# io_board.net
KiCad netlist of a schematic drawn in EAGLE
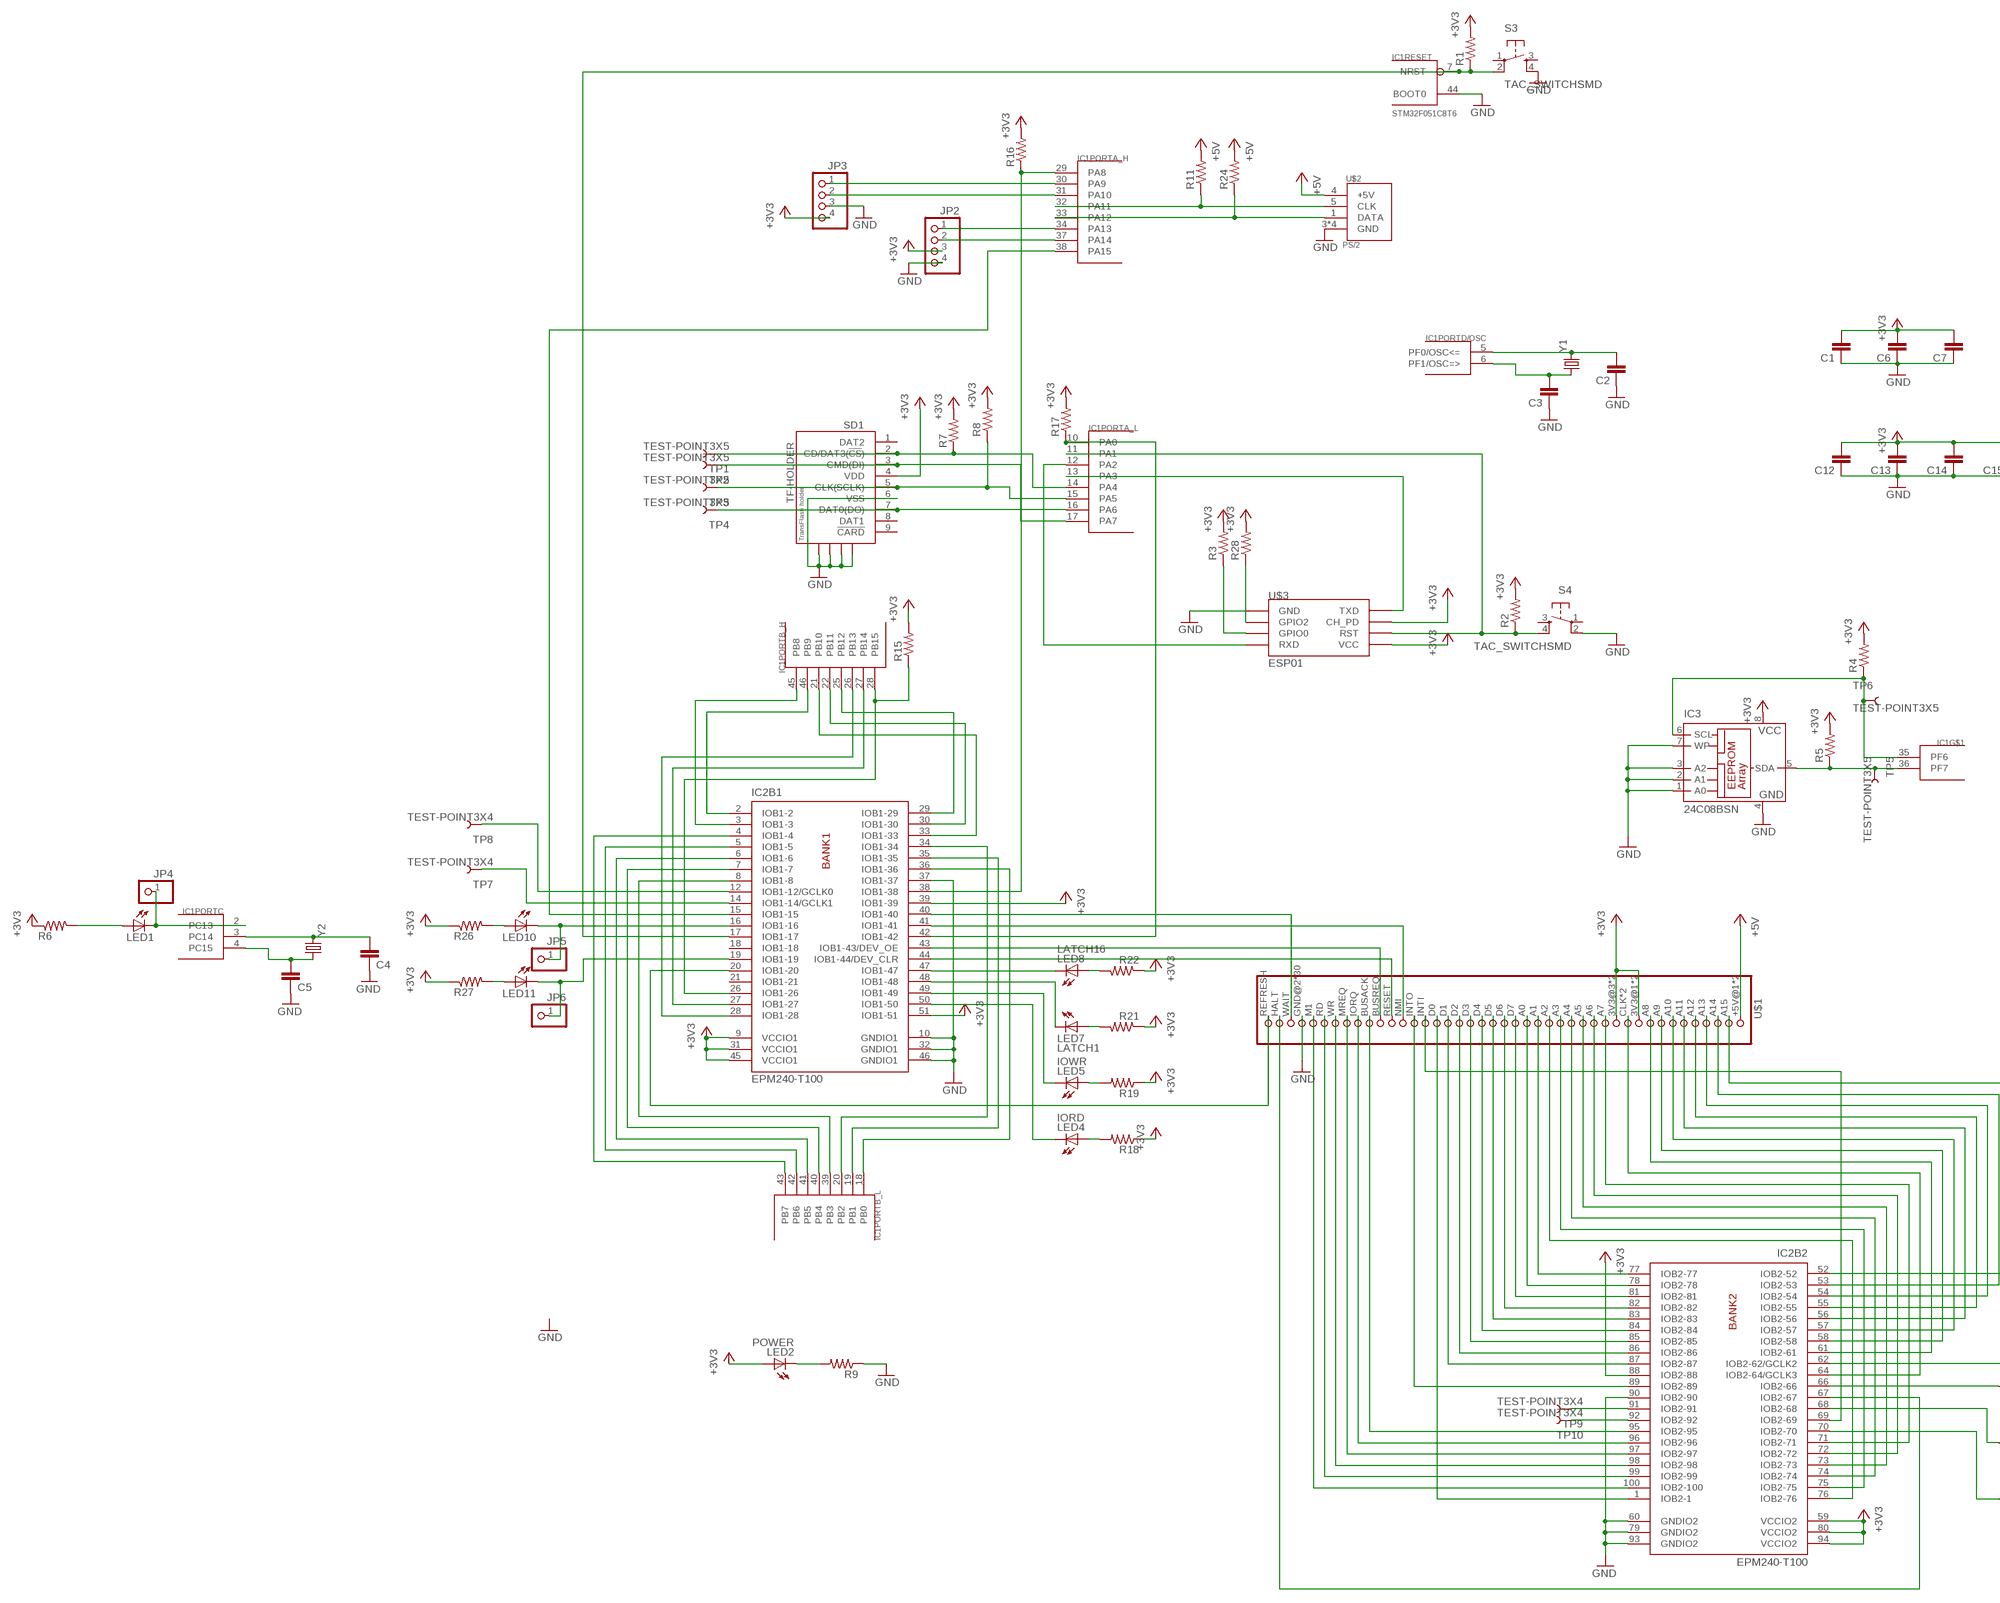
[diagram p0: schematic, sheet 1, part 1 of 2]
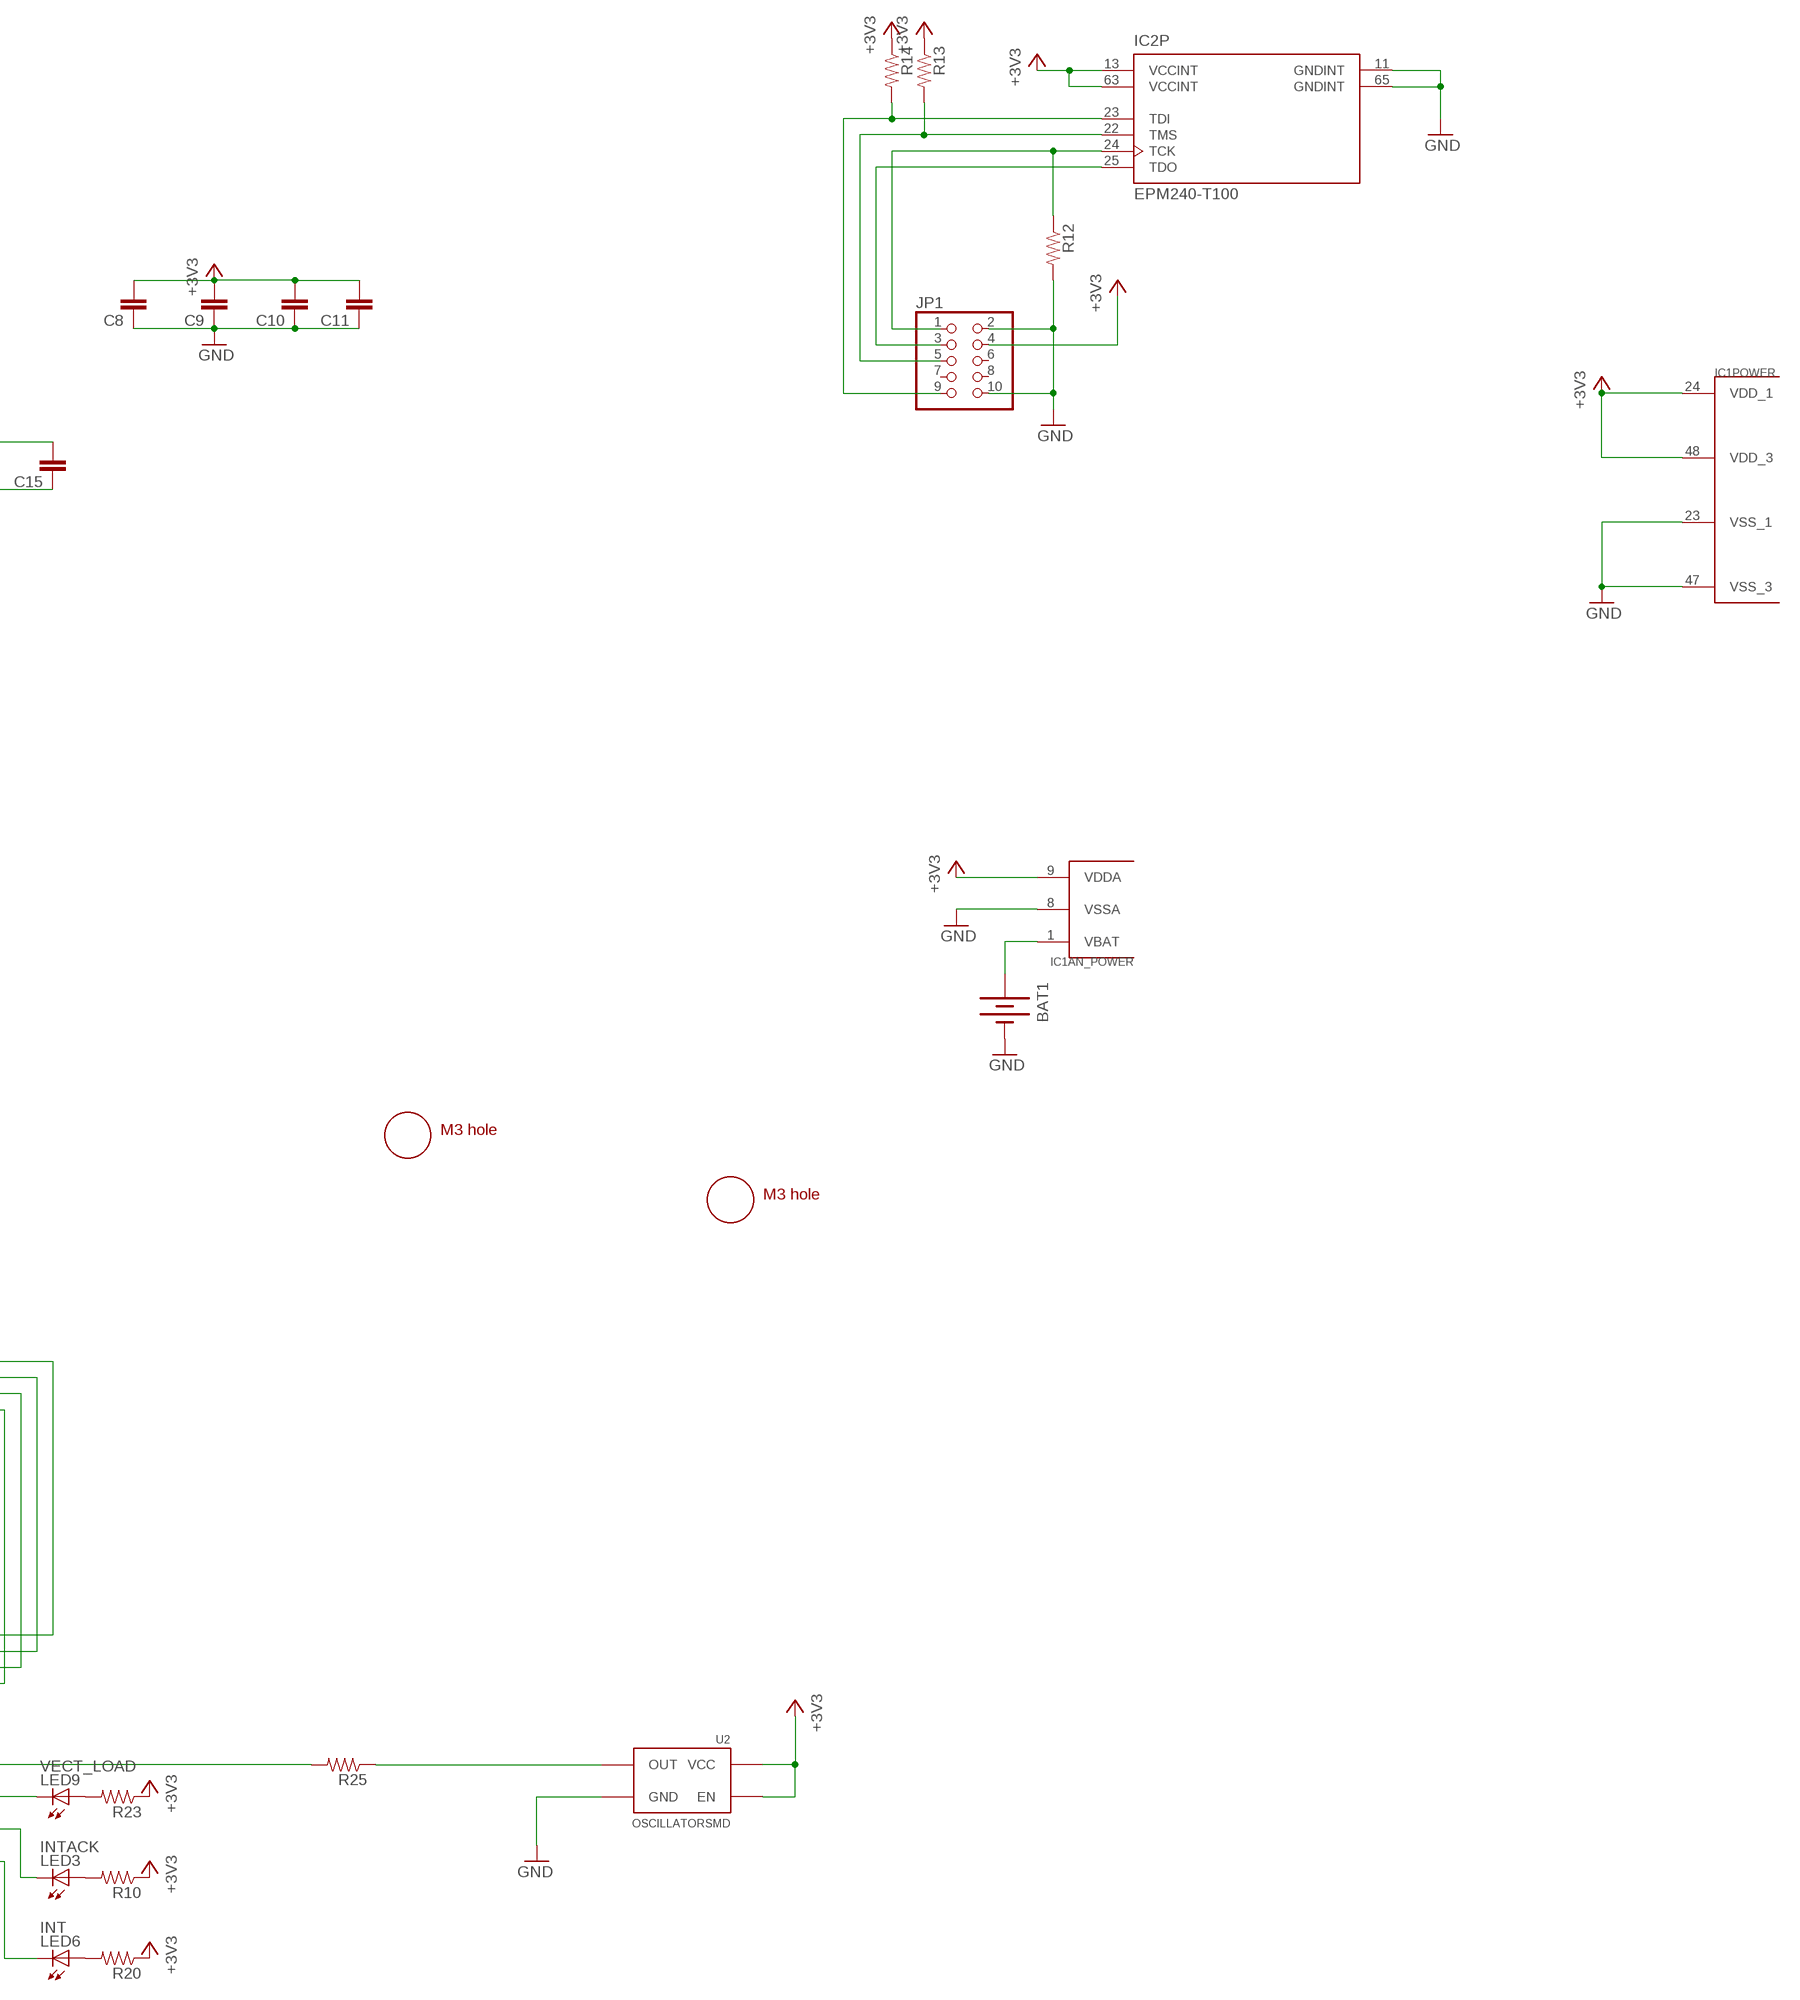
[diagram p1: schematic, sheet 1, part 2 of 2]

(export (version "E")
  (design (tool "Eeschema 10.0.6"))
  (components
    (comp (ref "BAT1")
      (value "BATTERY20PTH")
      (footprint "eagle-import:BATTCOM_20MM_PTH")
      (libsource (lib "eagle-import") (part "BATTERY20PTH"))
    )
    (comp (ref "C1")
      (value "CAP0805")
      (footprint "eagle-import:0805")
      (libsource (lib "eagle-import") (part "CAP0805"))
    )
    (comp (ref "C2")
      (value "CAP0805")
      (footprint "eagle-import:0805")
      (libsource (lib "eagle-import") (part "CAP0805"))
    )
    (comp (ref "C3")
      (value "CAP0805")
      (footprint "eagle-import:0805")
      (libsource (lib "eagle-import") (part "CAP0805"))
    )
    (comp (ref "C4")
      (value "CAP0805")
      (footprint "eagle-import:0805")
      (libsource (lib "eagle-import") (part "CAP0805"))
    )
    (comp (ref "C5")
      (value "CAP0805")
      (footprint "eagle-import:0805")
      (libsource (lib "eagle-import") (part "CAP0805"))
    )
    (comp (ref "C6")
      (value "CAP0805")
      (footprint "eagle-import:0805")
      (libsource (lib "eagle-import") (part "CAP0805"))
    )
    (comp (ref "C7")
      (value "CAP0805")
      (footprint "eagle-import:0805")
      (libsource (lib "eagle-import") (part "CAP0805"))
    )
    (comp (ref "C8")
      (value "CAP0805")
      (footprint "eagle-import:0805")
      (libsource (lib "eagle-import") (part "CAP0805"))
    )
    (comp (ref "C9")
      (value "CAP0805")
      (footprint "eagle-import:0805")
      (libsource (lib "eagle-import") (part "CAP0805"))
    )
    (comp (ref "C10")
      (value "CAP0805")
      (footprint "eagle-import:0805")
      (libsource (lib "eagle-import") (part "CAP0805"))
    )
    (comp (ref "C11")
      (value "CAP0805")
      (footprint "eagle-import:0805")
      (libsource (lib "eagle-import") (part "CAP0805"))
    )
    (comp (ref "C12")
      (value "CAP0805")
      (footprint "eagle-import:0805")
      (libsource (lib "eagle-import") (part "CAP0805"))
    )
    (comp (ref "C13")
      (value "CAP0805")
      (footprint "eagle-import:0805")
      (libsource (lib "eagle-import") (part "CAP0805"))
    )
    (comp (ref "C14")
      (value "CAP0805")
      (footprint "eagle-import:0805")
      (libsource (lib "eagle-import") (part "CAP0805"))
    )
    (comp (ref "C15")
      (value "CAP0805")
      (footprint "eagle-import:0805")
      (libsource (lib "eagle-import") (part "CAP0805"))
    )
    (comp (ref "IC1")
      (value "STM32F051C8T6")
      (footprint "eagle-import:TQFP48")
      (libsource (lib "eagle-import") (part "STM32F051C8T6"))
    )
    (comp (ref "IC2")
      (value "EPM240-T100")
      (footprint "eagle-import:TQFP100")
      (libsource (lib "eagle-import") (part "EPM240-T100"))
    )
    (comp (ref "IC3")
      (value "24C08BSN")
      (footprint "eagle-import:SO-08")
      (fields (field (name "MPN") "AT24C08BN-SH-B"))
      (libsource (lib "eagle-import") (part "24SNC08B"))
    )
    (comp (ref "JP1")
      (value "PINHD-2X5")
      (footprint "eagle-import:2X05")
      (libsource (lib "eagle-import") (part "PINHD-2X5"))
    )
    (comp (ref "JP2")
      (value "PINHD-1X4/90")
      (footprint "eagle-import:1X04_90")
      (libsource (lib "eagle-import") (part "PINHD-1X4/90"))
    )
    (comp (ref "JP3")
      (value "PINHD-1X4/90")
      (footprint "eagle-import:1X04_90")
      (libsource (lib "eagle-import") (part "PINHD-1X4/90"))
    )
    (comp (ref "JP4")
      (value "PINHD-1X1")
      (footprint "eagle-import:1X01")
      (libsource (lib "eagle-import") (part "PINHD-1X1"))
    )
    (comp (ref "JP5")
      (value "PINHD-1X1")
      (footprint "eagle-import:1X01")
      (libsource (lib "eagle-import") (part "PINHD-1X1"))
    )
    (comp (ref "JP6")
      (value "PINHD-1X1")
      (footprint "eagle-import:1X01")
      (libsource (lib "eagle-import") (part "PINHD-1X1"))
    )
    (comp (ref "LED1")
      (value "LEDCHIP-LED0805")
      (footprint "eagle-import:CHIP-LED0805")
      (libsource (lib "eagle-import") (part "LEDCHIP-LED0805"))
    )
    (comp (ref "LED2")
      (value "POWER")
      (footprint "eagle-import:CHIPLED_0805")
      (libsource (lib "eagle-import") (part "LEDCHIPLED_0805"))
    )
    (comp (ref "LED3")
      (value "INTACK")
      (footprint "eagle-import:CHIP-LED0805")
      (libsource (lib "eagle-import") (part "LEDCHIP-LED0805"))
    )
    (comp (ref "LED4")
      (value "IORD")
      (footprint "eagle-import:CHIP-LED0805")
      (libsource (lib "eagle-import") (part "LEDCHIP-LED0805"))
    )
    (comp (ref "LED5")
      (value "IOWR")
      (footprint "eagle-import:CHIP-LED0805")
      (libsource (lib "eagle-import") (part "LEDCHIP-LED0805"))
    )
    (comp (ref "LED6")
      (value "INT")
      (footprint "eagle-import:CHIP-LED0805")
      (libsource (lib "eagle-import") (part "LEDCHIP-LED0805"))
    )
    (comp (ref "LED7")
      (value "LATCH1")
      (footprint "eagle-import:CHIP-LED0805")
      (libsource (lib "eagle-import") (part "LEDCHIP-LED0805"))
    )
    (comp (ref "LED8")
      (value "LATCH16")
      (footprint "eagle-import:CHIP-LED0805")
      (libsource (lib "eagle-import") (part "LEDCHIP-LED0805"))
    )
    (comp (ref "LED9")
      (value "VECT_LOAD")
      (footprint "eagle-import:CHIP-LED0805")
      (libsource (lib "eagle-import") (part "LEDCHIP-LED0805"))
    )
    (comp (ref "LED10")
      (value "LEDCHIP-LED0805")
      (footprint "eagle-import:CHIP-LED0805")
      (libsource (lib "eagle-import") (part "LEDCHIP-LED0805"))
    )
    (comp (ref "LED11")
      (value "LEDCHIP-LED0805")
      (footprint "eagle-import:CHIP-LED0805")
      (libsource (lib "eagle-import") (part "LEDCHIP-LED0805"))
    )
    (comp (ref "R1")
      (value "RESISTOR0805-RES")
      (footprint "eagle-import:0805")
      (libsource (lib "eagle-import") (part "RESISTOR0805-RES"))
    )
    (comp (ref "R2")
      (value "RESISTOR0805-RES")
      (footprint "eagle-import:0805")
      (libsource (lib "eagle-import") (part "RESISTOR0805-RES"))
    )
    (comp (ref "R3")
      (value "RESISTOR0805-RES")
      (footprint "eagle-import:0805")
      (libsource (lib "eagle-import") (part "RESISTOR0805-RES"))
    )
    (comp (ref "R4")
      (value "RESISTOR0805-RES")
      (footprint "eagle-import:0805")
      (libsource (lib "eagle-import") (part "RESISTOR0805-RES"))
    )
    (comp (ref "R5")
      (value "RESISTOR0805-RES")
      (footprint "eagle-import:0805")
      (libsource (lib "eagle-import") (part "RESISTOR0805-RES"))
    )
    (comp (ref "R6")
      (value "RESISTOR0805-RES")
      (footprint "eagle-import:0805")
      (libsource (lib "eagle-import") (part "RESISTOR0805-RES"))
    )
    (comp (ref "R7")
      (value "RESISTOR0805-RES")
      (footprint "eagle-import:0805")
      (libsource (lib "eagle-import") (part "RESISTOR0805-RES"))
    )
    (comp (ref "R8")
      (value "RESISTOR0805-RES")
      (footprint "eagle-import:0805")
      (libsource (lib "eagle-import") (part "RESISTOR0805-RES"))
    )
    (comp (ref "R9")
      (value "RESISTOR0805-RES")
      (footprint "eagle-import:0805")
      (libsource (lib "eagle-import") (part "RESISTOR0805-RES"))
    )
    (comp (ref "R10")
      (value "RESISTOR0805-RES")
      (footprint "eagle-import:0805")
      (libsource (lib "eagle-import") (part "RESISTOR0805-RES"))
    )
    (comp (ref "R11")
      (value "RESISTOR0805-RES")
      (footprint "eagle-import:0805")
      (libsource (lib "eagle-import") (part "RESISTOR0805-RES"))
    )
    (comp (ref "R12")
      (value "RESISTOR0805-RES")
      (footprint "eagle-import:0805")
      (libsource (lib "eagle-import") (part "RESISTOR0805-RES"))
    )
    (comp (ref "R13")
      (value "RESISTOR0805-RES")
      (footprint "eagle-import:0805")
      (libsource (lib "eagle-import") (part "RESISTOR0805-RES"))
    )
    (comp (ref "R14")
      (value "RESISTOR0805-RES")
      (footprint "eagle-import:0805")
      (libsource (lib "eagle-import") (part "RESISTOR0805-RES"))
    )
    (comp (ref "R15")
      (value "RESISTOR0805-RES")
      (footprint "eagle-import:0805")
      (libsource (lib "eagle-import") (part "RESISTOR0805-RES"))
    )
    (comp (ref "R16")
      (value "RESISTOR0805-RES")
      (footprint "eagle-import:0805")
      (libsource (lib "eagle-import") (part "RESISTOR0805-RES"))
    )
    (comp (ref "R17")
      (value "RESISTOR0805-RES")
      (footprint "eagle-import:0805")
      (libsource (lib "eagle-import") (part "RESISTOR0805-RES"))
    )
    (comp (ref "R18")
      (value "RESISTOR0805-RES")
      (footprint "eagle-import:0805")
      (libsource (lib "eagle-import") (part "RESISTOR0805-RES"))
    )
    (comp (ref "R19")
      (value "RESISTOR0805-RES")
      (footprint "eagle-import:0805")
      (libsource (lib "eagle-import") (part "RESISTOR0805-RES"))
    )
    (comp (ref "R20")
      (value "RESISTOR0805-RES")
      (footprint "eagle-import:0805")
      (libsource (lib "eagle-import") (part "RESISTOR0805-RES"))
    )
    (comp (ref "R21")
      (value "RESISTOR0805-RES")
      (footprint "eagle-import:0805")
      (libsource (lib "eagle-import") (part "RESISTOR0805-RES"))
    )
    (comp (ref "R22")
      (value "RESISTOR0805-RES")
      (footprint "eagle-import:0805")
      (libsource (lib "eagle-import") (part "RESISTOR0805-RES"))
    )
    (comp (ref "R23")
      (value "RESISTOR0805-RES")
      (footprint "eagle-import:0805")
      (libsource (lib "eagle-import") (part "RESISTOR0805-RES"))
    )
    (comp (ref "R24")
      (value "RESISTOR0805-RES")
      (footprint "eagle-import:0805")
      (libsource (lib "eagle-import") (part "RESISTOR0805-RES"))
    )
    (comp (ref "R25")
      (value "RESISTOR0805-RES")
      (footprint "eagle-import:0805")
      (libsource (lib "eagle-import") (part "RESISTOR0805-RES"))
    )
    (comp (ref "R26")
      (value "RESISTOR0805-RES")
      (footprint "eagle-import:0805")
      (libsource (lib "eagle-import") (part "RESISTOR0805-RES"))
    )
    (comp (ref "R27")
      (value "RESISTOR0805-RES")
      (footprint "eagle-import:0805")
      (libsource (lib "eagle-import") (part "RESISTOR0805-RES"))
    )
    (comp (ref "R28")
      (value "RESISTOR0805-RES")
      (footprint "eagle-import:0805")
      (libsource (lib "eagle-import") (part "RESISTOR0805-RES"))
    )
    (comp (ref "S3")
      (value "TAC_SWITCHSMD")
      (footprint "eagle-import:TACTILE-SWITCH-SMD")
      (libsource (lib "eagle-import") (part "TAC_SWITCHSMD"))
    )
    (comp (ref "S4")
      (value "TAC_SWITCHSMD")
      (footprint "eagle-import:TACTILE-SWITCH-SMD")
      (libsource (lib "eagle-import") (part "TAC_SWITCHSMD"))
    )
    (comp (ref "SD1")
      (value "TF-HOLDER")
      (footprint "eagle-import:TF-PULL")
      (libsource (lib "eagle-import") (part "TF-HOLDER"))
    )
    (comp (ref "TP1")
      (value "TEST-POINT3X5")
      (footprint "eagle-import:PAD.03X.05")
      (libsource (lib "eagle-import") (part "TEST-POINT3X5"))
    )
    (comp (ref "TP2")
      (value "TEST-POINT3X5")
      (footprint "eagle-import:PAD.03X.05")
      (libsource (lib "eagle-import") (part "TEST-POINT3X5"))
    )
    (comp (ref "TP3")
      (value "TEST-POINT3X5")
      (footprint "eagle-import:PAD.03X.05")
      (libsource (lib "eagle-import") (part "TEST-POINT3X5"))
    )
    (comp (ref "TP4")
      (value "TEST-POINT3X5")
      (footprint "eagle-import:PAD.03X.05")
      (libsource (lib "eagle-import") (part "TEST-POINT3X5"))
    )
    (comp (ref "TP5")
      (value "TEST-POINT3X5")
      (footprint "eagle-import:PAD.03X.05")
      (libsource (lib "eagle-import") (part "TEST-POINT3X5"))
    )
    (comp (ref "TP6")
      (value "TEST-POINT3X5")
      (footprint "eagle-import:PAD.03X.05")
      (libsource (lib "eagle-import") (part "TEST-POINT3X5"))
    )
    (comp (ref "TP7")
      (value "TEST-POINT3X4")
      (footprint "eagle-import:PAD.03X.04")
      (libsource (lib "eagle-import") (part "TEST-POINT3X4"))
    )
    (comp (ref "TP8")
      (value "TEST-POINT3X4")
      (footprint "eagle-import:PAD.03X.04")
      (libsource (lib "eagle-import") (part "TEST-POINT3X4"))
    )
    (comp (ref "TP9")
      (value "TEST-POINT3X4")
      (footprint "eagle-import:PAD.03X.04")
      (libsource (lib "eagle-import") (part "TEST-POINT3X4"))
    )
    (comp (ref "TP10")
      (value "TEST-POINT3X4")
      (footprint "eagle-import:PAD.03X.04")
      (libsource (lib "eagle-import") (part "TEST-POINT3X4"))
    )
    (comp (ref "U$1")
      (value "FAP_BUS")
      (footprint "eagle-import:2X38")
      (libsource (lib "eagle-import") (part "FAP_BUS"))
    )
    (comp (ref "U$2")
      (value "PS/2")
      (footprint "eagle-import:PS_2")
      (libsource (lib "eagle-import") (part "PS/2"))
    )
    (comp (ref "U$3")
      (value "ESP01")
      (footprint "eagle-import:ESP01")
      (libsource (lib "eagle-import") (part "ESP01"))
    )
    (comp (ref "U$4")
      (value "M3_MOUNTING_HOLE")
      (footprint "eagle-import:M3_MOUNTING_HOLE_PACK")
      (libsource (lib "eagle-import") (part "M3_MOUNTING_HOLE"))
    )
    (comp (ref "U$5")
      (value "M3_MOUNTING_HOLE")
      (footprint "eagle-import:M3_MOUNTING_HOLE_PACK")
      (libsource (lib "eagle-import") (part "M3_MOUNTING_HOLE"))
    )
    (comp (ref "U2")
      (value "OSCILLATORSMD")
      (footprint "eagle-import:CRYSTAL-SMD-7X5")
      (libsource (lib "eagle-import") (part "OSCILLATORSMD"))
    )
    (comp (ref "Y1")
      (value "CRYSTALHC49US")
      (footprint "eagle-import:HC49US")
      (libsource (lib "eagle-import") (part "CRYSTALHC49US"))
    )
    (comp (ref "Y2")
      (value "CRYSTALTC26H_EZ")
      (footprint "eagle-import:TC26HEZ")
      (libsource (lib "eagle-import") (part "CRYSTALTC26H_EZ"))
    )
  )
  (nets
    (net (code "1") (name "+3V3") (class "Default")
      (node (ref "C1") (pin "2") (pinfunction "2_2") (pintype "passive"))
      (node (ref "C10") (pin "2") (pinfunction "2_2") (pintype "passive"))
      (node (ref "C11") (pin "2") (pinfunction "2_2") (pintype "passive"))
      (node (ref "C12") (pin "2") (pinfunction "2_2") (pintype "passive"))
      (node (ref "C13") (pin "2") (pinfunction "2_2") (pintype "passive"))
      (node (ref "C14") (pin "2") (pinfunction "2_2") (pintype "passive"))
      (node (ref "C15") (pin "2") (pinfunction "2_2") (pintype "passive"))
      (node (ref "C6") (pin "2") (pinfunction "2_2") (pintype "passive"))
      (node (ref "C7") (pin "2") (pinfunction "2_2") (pintype "passive"))
      (node (ref "C8") (pin "2") (pinfunction "2_2") (pintype "passive"))
      (node (ref "C9") (pin "2") (pinfunction "2_2") (pintype "passive"))
      (node (ref "IC1") (pin "24") (pinfunction "VDD_1_24") (pintype "power_in"))
      (node (ref "IC1") (pin "48") (pinfunction "VDD_3_48") (pintype "power_in"))
      (node (ref "IC1") (pin "9") (pinfunction "VDDA_9") (pintype "power_in"))
      (node (ref "IC2") (pin "13") (pinfunction "VCCINT_13") (pintype "power_in"))
      (node (ref "IC2") (pin "31") (pinfunction "VCCIO1_31") (pintype "power_in"))
      (node (ref "IC2") (pin "39") (pinfunction "IOB1-39_39") (pintype "bidirectional"))
      (node (ref "IC2") (pin "45") (pinfunction "VCCIO1_45") (pintype "power_in"))
      (node (ref "IC2") (pin "51") (pinfunction "IOB1-51_51") (pintype "bidirectional"))
      (node (ref "IC2") (pin "59") (pinfunction "VCCIO2_59") (pintype "power_in"))
      (node (ref "IC2") (pin "63") (pinfunction "VCCINT_63") (pintype "power_in"))
      (node (ref "IC2") (pin "80") (pinfunction "VCCIO2_80") (pintype "power_in"))
      (node (ref "IC2") (pin "88") (pinfunction "IOB2-88_88") (pintype "bidirectional"))
      (node (ref "IC2") (pin "9") (pinfunction "VCCIO1_9") (pintype "power_in"))
      (node (ref "IC2") (pin "94") (pinfunction "VCCIO2_94") (pintype "power_in"))
      (node (ref "IC3") (pin "8") (pinfunction "VCC_8") (pintype "power_in"))
      (node (ref "JP1") (pin "4") (pinfunction "4_4") (pintype "passive"))
      (node (ref "JP2") (pin "3") (pinfunction "3_3") (pintype "passive"))
      (node (ref "JP3") (pin "4") (pinfunction "4_4") (pintype "passive"))
      (node (ref "LED2") (pin "A") (pinfunction "A_A") (pintype "passive"))
      (node (ref "R1") (pin "2") (pinfunction "2_2") (pintype "passive"))
      (node (ref "R10") (pin "1") (pinfunction "1_1") (pintype "passive"))
      (node (ref "R13") (pin "1") (pinfunction "1_1") (pintype "passive"))
      (node (ref "R14") (pin "1") (pinfunction "1_1") (pintype "passive"))
      (node (ref "R15") (pin "2") (pinfunction "2_2") (pintype "passive"))
      (node (ref "R16") (pin "2") (pinfunction "2_2") (pintype "passive"))
      (node (ref "R17") (pin "2") (pinfunction "2_2") (pintype "passive"))
      (node (ref "R18") (pin "1") (pinfunction "1_1") (pintype "passive"))
      (node (ref "R19") (pin "1") (pinfunction "1_1") (pintype "passive"))
      (node (ref "R2") (pin "2") (pinfunction "2_2") (pintype "passive"))
      (node (ref "R20") (pin "1") (pinfunction "1_1") (pintype "passive"))
      (node (ref "R21") (pin "1") (pinfunction "1_1") (pintype "passive"))
      (node (ref "R22") (pin "1") (pinfunction "1_1") (pintype "passive"))
      (node (ref "R23") (pin "1") (pinfunction "1_1") (pintype "passive"))
      (node (ref "R26") (pin "1") (pinfunction "1_1") (pintype "passive"))
      (node (ref "R27") (pin "1") (pinfunction "1_1") (pintype "passive"))
      (node (ref "R28") (pin "2") (pinfunction "2_2") (pintype "passive"))
      (node (ref "R3") (pin "2") (pinfunction "2_2") (pintype "passive"))
      (node (ref "R4") (pin "2") (pinfunction "2_2") (pintype "passive"))
      (node (ref "R5") (pin "2") (pinfunction "2_2") (pintype "passive"))
      (node (ref "R6") (pin "1") (pinfunction "1_1") (pintype "passive"))
      (node (ref "R7") (pin "2") (pinfunction "2_2") (pintype "passive"))
      (node (ref "R8") (pin "2") (pinfunction "2_2") (pintype "passive"))
      (node (ref "SD1") (pin "4") (pinfunction "VDD_4") (pintype "power_in"))
      (node (ref "U$1") (pin "3V3@1") (pinfunction "10_3V3@1") (pintype "passive"))
      (node (ref "U$1") (pin "3V3@2") (pinfunction "10_3V3@2") (pintype "passive"))
      (node (ref "U$1") (pin "3V3@3") (pinfunction "12_3V3@3") (pintype "passive"))
      (node (ref "U$1") (pin "3V3@4") (pinfunction "12_3V3@4") (pintype "passive"))
      (node (ref "U$3") (pin "CH_PD") (pinfunction "CH_PD_CH_PD") (pintype "bidirectional"))
      (node (ref "U$3") (pin "VCC") (pinfunction "VCC_VCC") (pintype "bidirectional"))
      (node (ref "U2") (pin "P$1") (pinfunction "EN_P$1") (pintype "bidirectional"))
      (node (ref "U2") (pin "P$4") (pinfunction "VCC_P$4") (pintype "bidirectional"))
    )
    (net (code "2") (name "+5V") (class "Default")
      (node (ref "R11") (pin "2") (pinfunction "2_2") (pintype "passive"))
      (node (ref "R24") (pin "2") (pinfunction "2_2") (pintype "passive"))
      (node (ref "U$1") (pin "+5V@1") (pinfunction "1_+5V@1") (pintype "passive"))
      (node (ref "U$1") (pin "+5V@2") (pinfunction "1_+5V@2") (pintype "passive"))
      (node (ref "U$2") (pin "4") (pinfunction "+5V_4") (pintype "bidirectional"))
    )
    (net (code "3") (name "GND") (class "Default")
      (node (ref "BAT1") (pin "2") (pinfunction "-_2") (pintype "power_in"))
      (node (ref "C1") (pin "1") (pinfunction "1_1") (pintype "passive"))
      (node (ref "C10") (pin "1") (pinfunction "1_1") (pintype "passive"))
      (node (ref "C11") (pin "1") (pinfunction "1_1") (pintype "passive"))
      (node (ref "C12") (pin "1") (pinfunction "1_1") (pintype "passive"))
      (node (ref "C13") (pin "1") (pinfunction "1_1") (pintype "passive"))
      (node (ref "C14") (pin "1") (pinfunction "1_1") (pintype "passive"))
      (node (ref "C15") (pin "1") (pinfunction "1_1") (pintype "passive"))
      (node (ref "C2") (pin "1") (pinfunction "1_1") (pintype "passive"))
      (node (ref "C3") (pin "1") (pinfunction "1_1") (pintype "passive"))
      (node (ref "C4") (pin "1") (pinfunction "1_1") (pintype "passive"))
      (node (ref "C5") (pin "1") (pinfunction "1_1") (pintype "passive"))
      (node (ref "C6") (pin "1") (pinfunction "1_1") (pintype "passive"))
      (node (ref "C7") (pin "1") (pinfunction "1_1") (pintype "passive"))
      (node (ref "C8") (pin "1") (pinfunction "1_1") (pintype "passive"))
      (node (ref "C9") (pin "1") (pinfunction "1_1") (pintype "passive"))
      (node (ref "IC1") (pin "23") (pinfunction "VSS_1_23") (pintype "power_in"))
      (node (ref "IC1") (pin "44") (pinfunction "BOOT0_44") (pintype "input"))
      (node (ref "IC1") (pin "47") (pinfunction "VSS_3_47") (pintype "power_in"))
      (node (ref "IC1") (pin "8") (pinfunction "VSSA_8") (pintype "power_in"))
      (node (ref "IC2") (pin "10") (pinfunction "GNDIO1_10") (pintype "power_in"))
      (node (ref "IC2") (pin "11") (pinfunction "GNDINT_11") (pintype "power_in"))
      (node (ref "IC2") (pin "32") (pinfunction "GNDIO1_32") (pintype "power_in"))
      (node (ref "IC2") (pin "37") (pinfunction "IOB1-37_37") (pintype "bidirectional"))
      (node (ref "IC2") (pin "46") (pinfunction "GNDIO1_46") (pintype "power_in"))
      (node (ref "IC2") (pin "60") (pinfunction "GNDIO2_60") (pintype "power_in"))
      (node (ref "IC2") (pin "65") (pinfunction "GNDINT_65") (pintype "power_in"))
      (node (ref "IC2") (pin "79") (pinfunction "GNDIO2_79") (pintype "power_in"))
      (node (ref "IC2") (pin "90") (pinfunction "IOB2-90_90") (pintype "bidirectional"))
      (node (ref "IC2") (pin "93") (pinfunction "GNDIO2_93") (pintype "power_in"))
      (node (ref "IC3") (pin "1") (pinfunction "A0_1") (pintype "input"))
      (node (ref "IC3") (pin "2") (pinfunction "A1_2") (pintype "input"))
      (node (ref "IC3") (pin "3") (pinfunction "A2_3") (pintype "input"))
      (node (ref "IC3") (pin "4") (pinfunction "GND_4") (pintype "power_in"))
      (node (ref "IC3") (pin "7") (pinfunction "WP_7") (pintype "input"))
      (node (ref "JP1") (pin "10") (pinfunction "10_10") (pintype "passive"))
      (node (ref "JP1") (pin "2") (pinfunction "2_2") (pintype "passive"))
      (node (ref "JP2") (pin "4") (pinfunction "4_4") (pintype "passive"))
      (node (ref "JP3") (pin "3") (pinfunction "3_3") (pintype "passive"))
      (node (ref "R12") (pin "2") (pinfunction "2_2") (pintype "passive"))
      (node (ref "R9") (pin "1") (pinfunction "1_1") (pintype "passive"))
      (node (ref "S3") (pin "4") (pinfunction "4_4") (pintype "passive"))
      (node (ref "S4") (pin "2") (pinfunction "2_2") (pintype "passive"))
      (node (ref "SD1") (pin "6") (pinfunction "VSS_6") (pintype "power_in"))
      (node (ref "SD1") (pin "S1") (pinfunction "S1_S1") (pintype "passive"))
      (node (ref "SD1") (pin "S2") (pinfunction "S2_S2") (pintype "passive"))
      (node (ref "SD1") (pin "S3") (pinfunction "S3_S3") (pintype "passive"))
      (node (ref "SD1") (pin "S4") (pinfunction "S4_S4") (pintype "passive"))
      (node (ref "U$1") (pin "GND@13") (pinfunction "GND_GND@13") (pintype "passive"))
      (node (ref "U$1") (pin "GND@14") (pinfunction "GND_GND@14") (pintype "passive"))
      (node (ref "U$1") (pin "GND@15") (pinfunction "GND_GND@15") (pintype "passive"))
      (node (ref "U$1") (pin "GND@16") (pinfunction "GND_GND@16") (pintype "passive"))
      (node (ref "U$1") (pin "GND@17") (pinfunction "GND_GND@17") (pintype "passive"))
      (node (ref "U$1") (pin "GND@18") (pinfunction "GND_GND@18") (pintype "passive"))
      (node (ref "U$1") (pin "GND@19") (pinfunction "GND_GND@19") (pintype "passive"))
      (node (ref "U$1") (pin "GND@2") (pinfunction "GND_GND@2") (pintype "passive"))
      (node (ref "U$1") (pin "GND@20") (pinfunction "GND_GND@20") (pintype "passive"))
      (node (ref "U$1") (pin "GND@21") (pinfunction "GND_GND@21") (pintype "passive"))
      (node (ref "U$1") (pin "GND@22") (pinfunction "GND_GND@22") (pintype "passive"))
      (node (ref "U$1") (pin "GND@23") (pinfunction "GND_GND@23") (pintype "passive"))
      (node (ref "U$1") (pin "GND@24") (pinfunction "GND_GND@24") (pintype "passive"))
      (node (ref "U$1") (pin "GND@25") (pinfunction "GND_GND@25") (pintype "passive"))
      (node (ref "U$1") (pin "GND@26") (pinfunction "GND_GND@26") (pintype "passive"))
      (node (ref "U$1") (pin "GND@27") (pinfunction "GND_GND@27") (pintype "passive"))
      (node (ref "U$1") (pin "GND@28") (pinfunction "GND_GND@28") (pintype "passive"))
      (node (ref "U$1") (pin "GND@3") (pinfunction "GND_GND@3") (pintype "passive"))
      (node (ref "U$1") (pin "GND@30") (pinfunction "GND_GND@30") (pintype "passive"))
      (node (ref "U$1") (pin "GND@34") (pinfunction "GND_GND@34") (pintype "passive"))
      (node (ref "U$1") (pin "GND@35") (pinfunction "GND_GND@35") (pintype "passive"))
      (node (ref "U$1") (pin "GND@36") (pinfunction "GND_GND@36") (pintype "passive"))
      (node (ref "U$1") (pin "GND@37") (pinfunction "GND_GND@37") (pintype "passive"))
      (node (ref "U$1") (pin "GND@38") (pinfunction "GND_GND@38") (pintype "passive"))
      (node (ref "U$1") (pin "GND@4") (pinfunction "GND_GND@4") (pintype "passive"))
      (node (ref "U$1") (pin "GND@5") (pinfunction "GND_GND@5") (pintype "passive"))
      (node (ref "U$1") (pin "GND@6") (pinfunction "GND_GND@6") (pintype "passive"))
      (node (ref "U$1") (pin "GND@7") (pinfunction "GND_GND@7") (pintype "passive"))
      (node (ref "U$1") (pin "GND@8") (pinfunction "GND_GND@8") (pintype "passive"))
      (node (ref "U$1") (pin "GND@9") (pinfunction "GND_GND@9") (pintype "passive"))
      (node (ref "U$2") (pin "3") (pinfunction "GND_3") (pintype "bidirectional"))
      (node (ref "U$2") (pin "P$1") (pinfunction "GND_P$1") (pintype "bidirectional"))
      (node (ref "U$2") (pin "P$2") (pinfunction "GND_P$2") (pintype "bidirectional"))
      (node (ref "U$2") (pin "P$3") (pinfunction "GND_P$3") (pintype "bidirectional"))
      (node (ref "U$3") (pin "GND") (pinfunction "GND_GND") (pintype "bidirectional"))
      (node (ref "U2") (pin "P$2") (pinfunction "GND_P$2") (pintype "bidirectional"))
    )
    (net (code "4") (name "Net-(BAT1-+)") (class "Default")
      (node (ref "BAT1") (pin "1") (pinfunction "+_1") (pintype "power_in"))
      (node (ref "IC1") (pin "1") (pinfunction "VBAT_1") (pintype "power_in"))
    )
    (net (code "5") (name "Net-(IC1B-PF6)") (class "Default")
      (node (ref "IC1") (pin "35") (pinfunction "PF6_35") (pintype "bidirectional"))
      (node (ref "IC3") (pin "6") (pinfunction "SCL_6") (pintype "input"))
      (node (ref "R4") (pin "1") (pinfunction "1_1") (pintype "passive"))
      (node (ref "TP6") (pin "P$1") (pinfunction "1_P$1") (pintype "bidirectional"))
    )
    (net (code "6") (name "Net-(IC1B-PF7)") (class "Default")
      (node (ref "IC1") (pin "36") (pinfunction "PF7_36") (pintype "bidirectional"))
      (node (ref "IC3") (pin "5") (pinfunction "SDA_5") (pintype "bidirectional"))
      (node (ref "R5") (pin "1") (pinfunction "1_1") (pintype "passive"))
      (node (ref "TP5") (pin "P$1") (pinfunction "1_P$1") (pintype "bidirectional"))
    )
    (net (code "7") (name "Net-(IC1C-PA8)") (class "Default")
      (node (ref "IC1") (pin "29") (pinfunction "PA8_29") (pintype "bidirectional"))
      (node (ref "IC2") (pin "38") (pinfunction "IOB1-38_38") (pintype "bidirectional"))
      (node (ref "R16") (pin "1") (pinfunction "1_1") (pintype "passive"))
    )
    (net (code "8") (name "Net-(IC1C-PA9)") (class "Default")
      (node (ref "IC1") (pin "30") (pinfunction "PA9_30") (pintype "bidirectional"))
      (node (ref "JP3") (pin "1") (pinfunction "1_1") (pintype "passive"))
    )
    (net (code "9") (name "Net-(IC1C-PA10)") (class "Default")
      (node (ref "IC1") (pin "31") (pinfunction "PA10_31") (pintype "bidirectional"))
      (node (ref "JP3") (pin "2") (pinfunction "2_2") (pintype "passive"))
    )
    (net (code "10") (name "Net-(IC1C-PA11)") (class "Default")
      (node (ref "IC1") (pin "32") (pinfunction "PA11_32") (pintype "bidirectional"))
      (node (ref "R11") (pin "1") (pinfunction "1_1") (pintype "passive"))
      (node (ref "U$2") (pin "5") (pinfunction "CLK_5") (pintype "bidirectional"))
    )
    (net (code "11") (name "Net-(IC1C-PA12)") (class "Default")
      (node (ref "IC1") (pin "33") (pinfunction "PA12_33") (pintype "bidirectional"))
      (node (ref "R24") (pin "1") (pinfunction "1_1") (pintype "passive"))
      (node (ref "U$2") (pin "1") (pinfunction "DATA_1") (pintype "bidirectional"))
    )
    (net (code "12") (name "Net-(IC1C-PA13)") (class "Default")
      (node (ref "IC1") (pin "34") (pinfunction "PA13_34") (pintype "bidirectional"))
      (node (ref "JP2") (pin "1") (pinfunction "1_1") (pintype "passive"))
    )
    (net (code "13") (name "Net-(IC1C-PA14)") (class "Default")
      (node (ref "IC1") (pin "37") (pinfunction "PA14_37") (pintype "bidirectional"))
      (node (ref "JP2") (pin "2") (pinfunction "2_2") (pintype "passive"))
    )
    (net (code "14") (name "Net-(IC1C-PA15)") (class "Default")
      (node (ref "IC1") (pin "38") (pinfunction "PA15_38") (pintype "bidirectional"))
      (node (ref "IC2") (pin "15") (pinfunction "IOB1-15_15") (pintype "bidirectional"))
    )
    (net (code "15") (name "Net-(IC1D-PA0)") (class "Default")
      (node (ref "IC1") (pin "10") (pinfunction "PA0_10") (pintype "bidirectional"))
      (node (ref "IC2") (pin "42") (pinfunction "IOB1-42_42") (pintype "bidirectional"))
      (node (ref "R17") (pin "1") (pinfunction "1_1") (pintype "passive"))
    )
    (net (code "16") (name "Net-(IC1D-PA1)") (class "Default")
      (node (ref "IC1") (pin "11") (pinfunction "PA1_11") (pintype "bidirectional"))
      (node (ref "R2") (pin "1") (pinfunction "1_1") (pintype "passive"))
      (node (ref "S4") (pin "4") (pinfunction "4_4") (pintype "passive"))
      (node (ref "U$3") (pin "RST") (pinfunction "RST_RST") (pintype "bidirectional"))
    )
    (net (code "17") (name "Net-(IC1D-PA2)") (class "Default")
      (node (ref "IC1") (pin "12") (pinfunction "PA2_12") (pintype "bidirectional"))
      (node (ref "U$3") (pin "RX") (pinfunction "RXD_RX") (pintype "bidirectional"))
    )
    (net (code "18") (name "Net-(IC1D-PA3)") (class "Default")
      (node (ref "IC1") (pin "13") (pinfunction "PA3_13") (pintype "bidirectional"))
      (node (ref "U$3") (pin "TX") (pinfunction "TXD_TX") (pintype "bidirectional"))
    )
    (net (code "19") (name "Net-(IC1D-PA4)") (class "Default")
      (node (ref "IC1") (pin "14") (pinfunction "PA4_14") (pintype "bidirectional"))
      (node (ref "R7") (pin "1") (pinfunction "1_1") (pintype "passive"))
      (node (ref "SD1") (pin "2") (pinfunction "CD/DAT3(~{CS})_2") (pintype "bidirectional"))
      (node (ref "TP1") (pin "P$1") (pinfunction "1_P$1") (pintype "bidirectional"))
    )
    (net (code "20") (name "Net-(IC1D-PA5)") (class "Default")
      (node (ref "IC1") (pin "15") (pinfunction "PA5_15") (pintype "bidirectional"))
      (node (ref "R8") (pin "1") (pinfunction "1_1") (pintype "passive"))
      (node (ref "SD1") (pin "5") (pinfunction "CLK(SCLK)_5") (pintype "input"))
      (node (ref "TP3") (pin "P$1") (pinfunction "1_P$1") (pintype "bidirectional"))
    )
    (net (code "21") (name "Net-(IC1D-PA6)") (class "Default")
      (node (ref "IC1") (pin "16") (pinfunction "PA6_16") (pintype "bidirectional"))
      (node (ref "SD1") (pin "7") (pinfunction "DAT0(DO)_7") (pintype "bidirectional"))
      (node (ref "TP4") (pin "P$1") (pinfunction "1_P$1") (pintype "bidirectional"))
    )
    (net (code "22") (name "Net-(IC1D-PA7)") (class "Default")
      (node (ref "IC1") (pin "17") (pinfunction "PA7_17") (pintype "bidirectional"))
      (node (ref "SD1") (pin "3") (pinfunction "CMD(DI)_3") (pintype "bidirectional"))
      (node (ref "TP2") (pin "P$1") (pinfunction "1_P$1") (pintype "bidirectional"))
    )
    (net (code "23") (name "Net-(IC1E-PB8)") (class "Default")
      (node (ref "IC1") (pin "45") (pinfunction "PB8_45") (pintype "bidirectional"))
      (node (ref "IC2") (pin "3") (pinfunction "IOB1-3_3") (pintype "bidirectional"))
    )
    (net (code "24") (name "Net-(IC1E-PB9)") (class "Default")
      (node (ref "IC1") (pin "46") (pinfunction "PB9_46") (pintype "bidirectional"))
      (node (ref "IC2") (pin "2") (pinfunction "IOB1-2_2") (pintype "bidirectional"))
    )
    (net (code "25") (name "Net-(IC1E-PB10)") (class "Default")
      (node (ref "IC1") (pin "21") (pinfunction "PB10_21") (pintype "bidirectional"))
      (node (ref "IC2") (pin "33") (pinfunction "IOB1-33_33") (pintype "bidirectional"))
    )
    (net (code "26") (name "Net-(IC1E-PB11)") (class "Default")
      (node (ref "IC1") (pin "22") (pinfunction "PB11_22") (pintype "bidirectional"))
      (node (ref "IC2") (pin "30") (pinfunction "IOB1-30_30") (pintype "bidirectional"))
    )
    (net (code "27") (name "Net-(IC1E-PB12)") (class "Default")
      (node (ref "IC1") (pin "25") (pinfunction "PB12_25") (pintype "bidirectional"))
      (node (ref "IC2") (pin "29") (pinfunction "IOB1-29_29") (pintype "bidirectional"))
    )
    (net (code "28") (name "Net-(IC1E-PB13)") (class "Default")
      (node (ref "IC1") (pin "26") (pinfunction "PB13_26") (pintype "bidirectional"))
      (node (ref "IC2") (pin "28") (pinfunction "IOB1-28_28") (pintype "bidirectional"))
    )
    (net (code "29") (name "Net-(IC1E-PB14)") (class "Default")
      (node (ref "IC1") (pin "27") (pinfunction "PB14_27") (pintype "bidirectional"))
      (node (ref "IC2") (pin "27") (pinfunction "IOB1-27_27") (pintype "bidirectional"))
    )
    (net (code "30") (name "Net-(IC1E-PB15)") (class "Default")
      (node (ref "IC1") (pin "28") (pinfunction "PB15_28") (pintype "bidirectional"))
      (node (ref "IC2") (pin "26") (pinfunction "IOB1-26_26") (pintype "bidirectional"))
      (node (ref "R15") (pin "1") (pinfunction "1_1") (pintype "passive"))
    )
    (net (code "31") (name "Net-(IC1F-PB0)") (class "Default")
      (node (ref "IC1") (pin "18") (pinfunction "PB0_18") (pintype "bidirectional"))
      (node (ref "IC2") (pin "36") (pinfunction "IOB1-36_36") (pintype "bidirectional"))
    )
    (net (code "32") (name "Net-(IC1F-PB1)") (class "Default")
      (node (ref "IC1") (pin "19") (pinfunction "PB1_19") (pintype "bidirectional"))
      (node (ref "IC2") (pin "35") (pinfunction "IOB1-35_35") (pintype "bidirectional"))
    )
    (net (code "33") (name "Net-(IC1F-PB2)") (class "Default")
      (node (ref "IC1") (pin "20") (pinfunction "PB2_20") (pintype "bidirectional"))
      (node (ref "IC2") (pin "34") (pinfunction "IOB1-34_34") (pintype "bidirectional"))
    )
    (net (code "34") (name "Net-(IC1F-PB3)") (class "Default")
      (node (ref "IC1") (pin "39") (pinfunction "PB3_39") (pintype "bidirectional"))
      (node (ref "IC2") (pin "8") (pinfunction "IOB1-8_8") (pintype "bidirectional"))
    )
    (net (code "35") (name "Net-(IC1F-PB4)") (class "Default")
      (node (ref "IC1") (pin "40") (pinfunction "PB4_40") (pintype "bidirectional"))
      (node (ref "IC2") (pin "7") (pinfunction "IOB1-7_7") (pintype "bidirectional"))
    )
    (net (code "36") (name "Net-(IC1F-PB5)") (class "Default")
      (node (ref "IC1") (pin "41") (pinfunction "PB5_41") (pintype "bidirectional"))
      (node (ref "IC2") (pin "6") (pinfunction "IOB1-6_6") (pintype "bidirectional"))
    )
    (net (code "37") (name "Net-(IC1F-PB6)") (class "Default")
      (node (ref "IC1") (pin "42") (pinfunction "PB6_42") (pintype "bidirectional"))
      (node (ref "IC2") (pin "5") (pinfunction "IOB1-5_5") (pintype "bidirectional"))
    )
    (net (code "38") (name "Net-(IC1F-PB7)") (class "Default")
      (node (ref "IC1") (pin "43") (pinfunction "PB7_43") (pintype "bidirectional"))
      (node (ref "IC2") (pin "4") (pinfunction "IOB1-4_4") (pintype "bidirectional"))
    )
    (net (code "39") (name "Net-(IC1G-PC13)") (class "Default")
      (node (ref "IC1") (pin "2") (pinfunction "PC13_2") (pintype "bidirectional"))
      (node (ref "JP4") (pin "1") (pinfunction "1_1") (pintype "passive"))
      (node (ref "LED1") (pin "C") (pinfunction "C_C") (pintype "passive"))
    )
    (net (code "40") (name "Net-(IC1G-PC14)") (class "Default")
      (node (ref "C4") (pin "2") (pinfunction "2_2") (pintype "passive"))
      (node (ref "IC1") (pin "3") (pinfunction "PC14_3") (pintype "bidirectional"))
      (node (ref "Y2") (pin "2") (pinfunction "2_2") (pintype "passive"))
    )
    (net (code "41") (name "Net-(IC1G-PC15)") (class "Default")
      (node (ref "C5") (pin "2") (pinfunction "2_2") (pintype "passive"))
      (node (ref "IC1") (pin "4") (pinfunction "PC15_4") (pintype "bidirectional"))
      (node (ref "Y2") (pin "1") (pinfunction "1_1") (pintype "passive"))
    )
    (net (code "42") (name "Net-(IC1H-PF0{slash}OSC<=)") (class "Default")
      (node (ref "C2") (pin "2") (pinfunction "2_2") (pintype "passive"))
      (node (ref "IC1") (pin "5") (pinfunction "PF0/OSC<=_5") (pintype "bidirectional"))
      (node (ref "Y1") (pin "2") (pinfunction "2_2") (pintype "passive"))
    )
    (net (code "43") (name "Net-(IC1H-PF1{slash}OSC=>)") (class "Default")
      (node (ref "C3") (pin "2") (pinfunction "2_2") (pintype "passive"))
      (node (ref "IC1") (pin "6") (pinfunction "PF1/OSC=>_6") (pintype "bidirectional"))
      (node (ref "Y1") (pin "1") (pinfunction "1_1") (pintype "passive"))
    )
    (net (code "44") (name "Net-(IC1J-NRST)") (class "Default")
      (node (ref "IC1") (pin "7") (pinfunction "NRST_7") (pintype "input"))
      (node (ref "IC2") (pin "17") (pinfunction "IOB1-17_17") (pintype "bidirectional"))
      (node (ref "R1") (pin "1") (pinfunction "1_1") (pintype "passive"))
      (node (ref "S3") (pin "2") (pinfunction "2_2") (pintype "passive"))
    )
    (net (code "45") (name "Net-(IC2A-IOB1-12{slash}GCLK0)") (class "Default")
      (node (ref "IC2") (pin "12") (pinfunction "IOB1-12/GCLK0_12") (pintype "bidirectional"))
      (node (ref "TP8") (pin "P$1") (pinfunction "1_P$1") (pintype "bidirectional"))
    )
    (net (code "46") (name "Net-(IC2A-IOB1-14{slash}GCLK1)") (class "Default")
      (node (ref "IC2") (pin "14") (pinfunction "IOB1-14/GCLK1_14") (pintype "bidirectional"))
      (node (ref "TP7") (pin "P$1") (pinfunction "1_P$1") (pintype "bidirectional"))
    )
    (net (code "47") (name "Net-(IC2A-IOB1-16)") (class "Default")
      (node (ref "IC2") (pin "16") (pinfunction "IOB1-16_16") (pintype "bidirectional"))
      (node (ref "JP5") (pin "1") (pinfunction "1_1") (pintype "passive"))
      (node (ref "LED10") (pin "C") (pinfunction "C_C") (pintype "passive"))
    )
    (net (code "48") (name "Net-(IC2A-IOB1-19)") (class "Default")
      (node (ref "IC2") (pin "19") (pinfunction "IOB1-19_19") (pintype "bidirectional"))
      (node (ref "JP6") (pin "1") (pinfunction "1_1") (pintype "passive"))
      (node (ref "LED11") (pin "C") (pinfunction "C_C") (pintype "passive"))
    )
    (net (code "49") (name "Net-(IC2A-IOB1-20)") (class "Default")
      (node (ref "IC2") (pin "20") (pinfunction "IOB1-20_20") (pintype "bidirectional"))
      (node (ref "U$1") (pin "REFRESH") (pinfunction "42_REFRESH") (pintype "passive"))
    )
    (net (code "50") (name "Net-(IC2A-IOB1-40)") (class "Default")
      (node (ref "IC2") (pin "40") (pinfunction "IOB1-40_40") (pintype "bidirectional"))
      (node (ref "U$1") (pin "WAIT") (pinfunction "40_WAIT") (pintype "passive"))
    )
    (net (code "51") (name "Net-(IC2A-IOB1-41)") (class "Default")
      (node (ref "IC2") (pin "41") (pinfunction "IOB1-41_41") (pintype "bidirectional"))
      (node (ref "U$1") (pin "NMI") (pinfunction "30_NMI") (pintype "passive"))
    )
    (net (code "52") (name "Net-(IC2A-IOB1-43{slash}DEV_OE)") (class "Default")
      (node (ref "IC2") (pin "43") (pinfunction "IOB1-43/DEV_OE_43") (pintype "bidirectional"))
      (node (ref "U$1") (pin "BUSREQ") (pinfunction "32_BUSREQ") (pintype "passive"))
    )
    (net (code "53") (name "Net-(IC2A-IOB1-44{slash}DEV_CLR)") (class "Default")
      (node (ref "IC2") (pin "44") (pinfunction "IOB1-44/DEV_CLR_44") (pintype "bidirectional"))
      (node (ref "U$1") (pin "RESET") (pinfunction "31_RESET") (pintype "passive"))
    )
    (net (code "54") (name "Net-(IC2A-IOB1-47)") (class "Default")
      (node (ref "IC2") (pin "47") (pinfunction "IOB1-47_47") (pintype "bidirectional"))
      (node (ref "LED8") (pin "C") (pinfunction "C_C") (pintype "passive"))
    )
    (net (code "55") (name "Net-(IC2A-IOB1-48)") (class "Default")
      (node (ref "IC2") (pin "48") (pinfunction "IOB1-48_48") (pintype "bidirectional"))
      (node (ref "LED7") (pin "C") (pinfunction "C_C") (pintype "passive"))
    )
    (net (code "56") (name "Net-(IC2A-IOB1-49)") (class "Default")
      (node (ref "IC2") (pin "49") (pinfunction "IOB1-49_49") (pintype "bidirectional"))
      (node (ref "LED5") (pin "C") (pinfunction "C_C") (pintype "passive"))
    )
    (net (code "57") (name "Net-(IC2A-IOB1-50)") (class "Default")
      (node (ref "IC2") (pin "50") (pinfunction "IOB1-50_50") (pintype "bidirectional"))
      (node (ref "LED4") (pin "C") (pinfunction "C_C") (pintype "passive"))
    )
    (net (code "58") (name "Net-(IC2B-IOB2-1)") (class "Default")
      (node (ref "IC2") (pin "1") (pinfunction "IOB2-1_1") (pintype "bidirectional"))
      (node (ref "U$1") (pin "D0") (pinfunction "28_D0") (pintype "passive"))
    )
    (net (code "59") (name "Net-(IC2B-IOB2-52)") (class "Default")
      (node (ref "IC2") (pin "52") (pinfunction "IOB2-52_52") (pintype "bidirectional"))
      (node (ref "U$1") (pin "A15") (pinfunction "2_A15") (pintype "passive"))
    )
    (net (code "60") (name "Net-(IC2B-IOB2-53)") (class "Default")
      (node (ref "IC2") (pin "53") (pinfunction "IOB2-53_53") (pintype "bidirectional"))
      (node (ref "U$1") (pin "A14") (pinfunction "3_A14") (pintype "passive"))
    )
    (net (code "61") (name "Net-(IC2B-IOB2-54)") (class "Default")
      (node (ref "IC2") (pin "54") (pinfunction "IOB2-54_54") (pintype "bidirectional"))
      (node (ref "U$1") (pin "A13") (pinfunction "4_A13") (pintype "passive"))
    )
    (net (code "62") (name "Net-(IC2B-IOB2-55)") (class "Default")
      (node (ref "IC2") (pin "55") (pinfunction "IOB2-55_55") (pintype "bidirectional"))
      (node (ref "U$1") (pin "A12") (pinfunction "5_A12") (pintype "passive"))
    )
    (net (code "63") (name "Net-(IC2B-IOB2-56)") (class "Default")
      (node (ref "IC2") (pin "56") (pinfunction "IOB2-56_56") (pintype "bidirectional"))
      (node (ref "U$1") (pin "A11") (pinfunction "6_A11") (pintype "passive"))
    )
    (net (code "64") (name "Net-(IC2B-IOB2-57)") (class "Default")
      (node (ref "IC2") (pin "57") (pinfunction "IOB2-57_57") (pintype "bidirectional"))
      (node (ref "U$1") (pin "A10") (pinfunction "7_A10") (pintype "passive"))
    )
    (net (code "65") (name "Net-(IC2B-IOB2-58)") (class "Default")
      (node (ref "IC2") (pin "58") (pinfunction "IOB2-58_58") (pintype "bidirectional"))
      (node (ref "U$1") (pin "A9") (pinfunction "8_A9") (pintype "passive"))
    )
    (net (code "66") (name "Net-(IC2B-IOB2-61)") (class "Default")
      (node (ref "IC2") (pin "61") (pinfunction "IOB2-61_61") (pintype "bidirectional"))
      (node (ref "U$1") (pin "A8") (pinfunction "9_A8") (pintype "passive"))
    )
    (net (code "67") (name "Net-(IC2B-IOB2-62{slash}GCLK2)") (class "Default")
      (node (ref "IC2") (pin "62") (pinfunction "IOB2-62/GCLK2_62") (pintype "bidirectional"))
      (node (ref "R25") (pin "2") (pinfunction "2_2") (pintype "passive"))
    )
    (net (code "68") (name "Net-(IC2B-IOB2-64{slash}GCLK3)") (class "Default")
      (node (ref "IC2") (pin "64") (pinfunction "IOB2-64/GCLK3_64") (pintype "bidirectional"))
      (node (ref "U$1") (pin "CLK") (pinfunction "11_CLK") (pintype "passive"))
      (node (ref "U$1") (pin "CLK@2") (pinfunction "11_CLK@2") (pintype "passive"))
    )
    (net (code "69") (name "Net-(IC2B-IOB2-66)") (class "Default")
      (node (ref "IC2") (pin "66") (pinfunction "IOB2-66_66") (pintype "bidirectional"))
      (node (ref "LED9") (pin "C") (pinfunction "C_C") (pintype "passive"))
    )
    (net (code "70") (name "Net-(IC2B-IOB2-67)") (class "Default")
      (node (ref "IC2") (pin "67") (pinfunction "IOB2-67_67") (pintype "bidirectional"))
      (node (ref "U$1") (pin "HALT") (pinfunction "41_HALT") (pintype "passive"))
    )
    (net (code "71") (name "Net-(IC2B-IOB2-68)") (class "Default")
      (node (ref "IC2") (pin "68") (pinfunction "IOB2-68_68") (pintype "bidirectional"))
      (node (ref "LED3") (pin "C") (pinfunction "C_C") (pintype "passive"))
    )
    (net (code "72") (name "Net-(IC2B-IOB2-69)") (class "Default")
      (node (ref "IC2") (pin "69") (pinfunction "IOB2-69_69") (pintype "bidirectional"))
      (node (ref "U$1") (pin "INTI") (pinfunction "29_INTI") (pintype "passive"))
    )
    (net (code "73") (name "Net-(IC2B-IOB2-70)") (class "Default")
      (node (ref "IC2") (pin "70") (pinfunction "IOB2-70_70") (pintype "bidirectional"))
      (node (ref "LED6") (pin "C") (pinfunction "C_C") (pintype "passive"))
    )
    (net (code "74") (name "Net-(IC2B-IOB2-71)") (class "Default")
      (node (ref "IC2") (pin "71") (pinfunction "IOB2-71_71") (pintype "bidirectional"))
      (node (ref "U$1") (pin "A7") (pinfunction "13_A7") (pintype "passive"))
    )
    (net (code "75") (name "Net-(IC2B-IOB2-72)") (class "Default")
      (node (ref "IC2") (pin "72") (pinfunction "IOB2-72_72") (pintype "bidirectional"))
      (node (ref "U$1") (pin "A6") (pinfunction "14_A6") (pintype "passive"))
    )
    (net (code "76") (name "Net-(IC2B-IOB2-73)") (class "Default")
      (node (ref "IC2") (pin "73") (pinfunction "IOB2-73_73") (pintype "bidirectional"))
      (node (ref "U$1") (pin "A5") (pinfunction "15_A5") (pintype "passive"))
    )
    (net (code "77") (name "Net-(IC2B-IOB2-74)") (class "Default")
      (node (ref "IC2") (pin "74") (pinfunction "IOB2-74_74") (pintype "bidirectional"))
      (node (ref "U$1") (pin "A4") (pinfunction "16_A4") (pintype "passive"))
    )
    (net (code "78") (name "Net-(IC2B-IOB2-75)") (class "Default")
      (node (ref "IC2") (pin "75") (pinfunction "IOB2-75_75") (pintype "bidirectional"))
      (node (ref "U$1") (pin "A3") (pinfunction "17_A3") (pintype "passive"))
    )
    (net (code "79") (name "Net-(IC2B-IOB2-76)") (class "Default")
      (node (ref "IC2") (pin "76") (pinfunction "IOB2-76_76") (pintype "bidirectional"))
      (node (ref "U$1") (pin "A2") (pinfunction "18_A2") (pintype "passive"))
    )
    (net (code "80") (name "Net-(IC2B-IOB2-77)") (class "Default")
      (node (ref "IC2") (pin "77") (pinfunction "IOB2-77_77") (pintype "bidirectional"))
      (node (ref "U$1") (pin "A1") (pinfunction "19_A1") (pintype "passive"))
    )
    (net (code "81") (name "Net-(IC2B-IOB2-78)") (class "Default")
      (node (ref "IC2") (pin "78") (pinfunction "IOB2-78_78") (pintype "bidirectional"))
      (node (ref "U$1") (pin "A0") (pinfunction "20_A0") (pintype "passive"))
    )
    (net (code "82") (name "Net-(IC2B-IOB2-81)") (class "Default")
      (node (ref "IC2") (pin "81") (pinfunction "IOB2-81_81") (pintype "bidirectional"))
      (node (ref "U$1") (pin "D7") (pinfunction "21_D7") (pintype "passive"))
    )
    (net (code "83") (name "Net-(IC2B-IOB2-82)") (class "Default")
      (node (ref "IC2") (pin "82") (pinfunction "IOB2-82_82") (pintype "bidirectional"))
      (node (ref "U$1") (pin "D6") (pinfunction "22_D6") (pintype "passive"))
    )
    (net (code "84") (name "Net-(IC2B-IOB2-83)") (class "Default")
      (node (ref "IC2") (pin "83") (pinfunction "IOB2-83_83") (pintype "bidirectional"))
      (node (ref "U$1") (pin "D5") (pinfunction "23_D5") (pintype "passive"))
    )
    (net (code "85") (name "Net-(IC2B-IOB2-84)") (class "Default")
      (node (ref "IC2") (pin "84") (pinfunction "IOB2-84_84") (pintype "bidirectional"))
      (node (ref "U$1") (pin "D4") (pinfunction "24_D4") (pintype "passive"))
    )
    (net (code "86") (name "Net-(IC2B-IOB2-85)") (class "Default")
      (node (ref "IC2") (pin "85") (pinfunction "IOB2-85_85") (pintype "bidirectional"))
      (node (ref "U$1") (pin "D3") (pinfunction "25_D3") (pintype "passive"))
    )
    (net (code "87") (name "Net-(IC2B-IOB2-86)") (class "Default")
      (node (ref "IC2") (pin "86") (pinfunction "IOB2-86_86") (pintype "bidirectional"))
      (node (ref "U$1") (pin "D2") (pinfunction "26_D2") (pintype "passive"))
    )
    (net (code "88") (name "Net-(IC2B-IOB2-87)") (class "Default")
      (node (ref "IC2") (pin "87") (pinfunction "IOB2-87_87") (pintype "bidirectional"))
      (node (ref "U$1") (pin "D1") (pinfunction "27_D1") (pintype "passive"))
    )
    (net (code "89") (name "Net-(IC2B-IOB2-89)") (class "Default")
      (node (ref "IC2") (pin "89") (pinfunction "IOB2-89_89") (pintype "bidirectional"))
      (node (ref "U$1") (pin "INTO") (pinfunction "39_INTO") (pintype "passive"))
    )
    (net (code "90") (name "Net-(IC2B-IOB2-91)") (class "Default")
      (node (ref "IC2") (pin "91") (pinfunction "IOB2-91_91") (pintype "bidirectional"))
      (node (ref "TP9") (pin "P$1") (pinfunction "1_P$1") (pintype "bidirectional"))
    )
    (net (code "91") (name "Net-(IC2B-IOB2-92)") (class "Default")
      (node (ref "IC2") (pin "92") (pinfunction "IOB2-92_92") (pintype "bidirectional"))
      (node (ref "TP10") (pin "P$1") (pinfunction "1_P$1") (pintype "bidirectional"))
    )
    (net (code "92") (name "Net-(IC2B-IOB2-95)") (class "Default")
      (node (ref "IC2") (pin "95") (pinfunction "IOB2-95_95") (pintype "bidirectional"))
      (node (ref "U$1") (pin "BUSACK") (pinfunction "33_BUSACK") (pintype "passive"))
    )
    (net (code "93") (name "Net-(IC2B-IOB2-96)") (class "Default")
      (node (ref "IC2") (pin "96") (pinfunction "IOB2-96_96") (pintype "bidirectional"))
      (node (ref "U$1") (pin "IORQ") (pinfunction "34_IORQ") (pintype "passive"))
    )
    (net (code "94") (name "Net-(IC2B-IOB2-97)") (class "Default")
      (node (ref "IC2") (pin "97") (pinfunction "IOB2-97_97") (pintype "bidirectional"))
      (node (ref "U$1") (pin "MREQ") (pinfunction "35_MREQ") (pintype "passive"))
    )
    (net (code "95") (name "Net-(IC2B-IOB2-98)") (class "Default")
      (node (ref "IC2") (pin "98") (pinfunction "IOB2-98_98") (pintype "bidirectional"))
      (node (ref "U$1") (pin "WR") (pinfunction "36_WR") (pintype "passive"))
    )
    (net (code "96") (name "Net-(IC2B-IOB2-99)") (class "Default")
      (node (ref "IC2") (pin "99") (pinfunction "IOB2-99_99") (pintype "bidirectional"))
      (node (ref "U$1") (pin "RD") (pinfunction "37_RD") (pintype "passive"))
    )
    (net (code "97") (name "Net-(IC2B-IOB2-100)") (class "Default")
      (node (ref "IC2") (pin "100") (pinfunction "IOB2-100_100") (pintype "bidirectional"))
      (node (ref "U$1") (pin "M1") (pinfunction "38_M1") (pintype "passive"))
    )
    (net (code "98") (name "Net-(IC2C-TCK)") (class "Default")
      (node (ref "IC2") (pin "24") (pinfunction "TCK_24") (pintype "input"))
      (node (ref "JP1") (pin "1") (pinfunction "1_1") (pintype "passive"))
      (node (ref "R12") (pin "1") (pinfunction "1_1") (pintype "passive"))
    )
    (net (code "99") (name "Net-(IC2C-TDI)") (class "Default")
      (node (ref "IC2") (pin "23") (pinfunction "TDI_23") (pintype "input"))
      (node (ref "JP1") (pin "9") (pinfunction "9_9") (pintype "passive"))
      (node (ref "R14") (pin "2") (pinfunction "2_2") (pintype "passive"))
    )
    (net (code "100") (name "Net-(IC2C-TDO)") (class "Default")
      (node (ref "IC2") (pin "25") (pinfunction "TDO_25") (pintype "output"))
      (node (ref "JP1") (pin "3") (pinfunction "3_3") (pintype "passive"))
    )
    (net (code "101") (name "Net-(IC2C-TMS)") (class "Default")
      (node (ref "IC2") (pin "22") (pinfunction "TMS_22") (pintype "input"))
      (node (ref "JP1") (pin "5") (pinfunction "5_5") (pintype "passive"))
      (node (ref "R13") (pin "2") (pinfunction "2_2") (pintype "passive"))
    )
    (net (code "102") (name "Net-(LED1-PadA)") (class "Default")
      (node (ref "LED1") (pin "A") (pinfunction "A_A") (pintype "passive"))
      (node (ref "R6") (pin "2") (pinfunction "2_2") (pintype "passive"))
    )
    (net (code "103") (name "Net-(LED2-PadC)") (class "Default")
      (node (ref "LED2") (pin "C") (pinfunction "C_C") (pintype "passive"))
      (node (ref "R9") (pin "2") (pinfunction "2_2") (pintype "passive"))
    )
    (net (code "104") (name "Net-(LED3-PadA)") (class "Default")
      (node (ref "LED3") (pin "A") (pinfunction "A_A") (pintype "passive"))
      (node (ref "R10") (pin "2") (pinfunction "2_2") (pintype "passive"))
    )
    (net (code "105") (name "Net-(LED4-PadA)") (class "Default")
      (node (ref "LED4") (pin "A") (pinfunction "A_A") (pintype "passive"))
      (node (ref "R18") (pin "2") (pinfunction "2_2") (pintype "passive"))
    )
    (net (code "106") (name "Net-(LED5-PadA)") (class "Default")
      (node (ref "LED5") (pin "A") (pinfunction "A_A") (pintype "passive"))
      (node (ref "R19") (pin "2") (pinfunction "2_2") (pintype "passive"))
    )
    (net (code "107") (name "Net-(LED6-PadA)") (class "Default")
      (node (ref "LED6") (pin "A") (pinfunction "A_A") (pintype "passive"))
      (node (ref "R20") (pin "2") (pinfunction "2_2") (pintype "passive"))
    )
    (net (code "108") (name "Net-(LED7-PadA)") (class "Default")
      (node (ref "LED7") (pin "A") (pinfunction "A_A") (pintype "passive"))
      (node (ref "R21") (pin "2") (pinfunction "2_2") (pintype "passive"))
    )
    (net (code "109") (name "Net-(LED8-PadA)") (class "Default")
      (node (ref "LED8") (pin "A") (pinfunction "A_A") (pintype "passive"))
      (node (ref "R22") (pin "2") (pinfunction "2_2") (pintype "passive"))
    )
    (net (code "110") (name "Net-(LED9-PadA)") (class "Default")
      (node (ref "LED9") (pin "A") (pinfunction "A_A") (pintype "passive"))
      (node (ref "R23") (pin "2") (pinfunction "2_2") (pintype "passive"))
    )
    (net (code "111") (name "Net-(LED10-PadA)") (class "Default")
      (node (ref "LED10") (pin "A") (pinfunction "A_A") (pintype "passive"))
      (node (ref "R26") (pin "2") (pinfunction "2_2") (pintype "passive"))
    )
    (net (code "112") (name "Net-(LED11-PadA)") (class "Default")
      (node (ref "LED11") (pin "A") (pinfunction "A_A") (pintype "passive"))
      (node (ref "R27") (pin "2") (pinfunction "2_2") (pintype "passive"))
    )
    (net (code "113") (name "Net-(R3-Pad1)") (class "Default")
      (node (ref "R3") (pin "1") (pinfunction "1_1") (pintype "passive"))
      (node (ref "U$3") (pin "GPIO0") (pinfunction "GPIO0_GPIO0") (pintype "bidirectional"))
    )
    (net (code "114") (name "Net-(R28-Pad1)") (class "Default")
      (node (ref "R28") (pin "1") (pinfunction "1_1") (pintype "passive"))
      (node (ref "U$3") (pin "GPIO2") (pinfunction "GPIO2_GPIO2") (pintype "bidirectional"))
    )
    (net (code "115") (name "Net-(U2-OUT)") (class "Default")
      (node (ref "R25") (pin "1") (pinfunction "1_1") (pintype "passive"))
      (node (ref "U2") (pin "P$3") (pinfunction "OUT_P$3") (pintype "bidirectional"))
    )
    (net (code "116") (name "unconnected-(IC2A-IOB1-18-Pad18)") (class "Default")
      (node (ref "IC2") (pin "18") (pinfunction "IOB1-18_18") (pintype "bidirectional"))
    )
    (net (code "117") (name "unconnected-(IC2A-IOB1-21-Pad21)") (class "Default")
      (node (ref "IC2") (pin "21") (pinfunction "IOB1-21_21") (pintype "bidirectional"))
    )
    (net (code "118") (name "unconnected-(JP1-Pad6)") (class "Default")
      (node (ref "JP1") (pin "6") (pinfunction "6_6") (pintype "passive"))
    )
    (net (code "119") (name "unconnected-(JP1-Pad7)") (class "Default")
      (node (ref "JP1") (pin "7") (pinfunction "7_7") (pintype "passive"))
    )
    (net (code "120") (name "unconnected-(JP1-Pad8)") (class "Default")
      (node (ref "JP1") (pin "8") (pinfunction "8_8") (pintype "passive"))
    )
    (net (code "121") (name "unconnected-(S3-Pad1)") (class "Default")
      (node (ref "S3") (pin "1") (pinfunction "1_1") (pintype "passive"))
    )
    (net (code "122") (name "unconnected-(S3-Pad3)") (class "Default")
      (node (ref "S3") (pin "3") (pinfunction "3_3") (pintype "passive"))
    )
    (net (code "123") (name "unconnected-(S4-Pad1)") (class "Default")
      (node (ref "S4") (pin "1") (pinfunction "1_1") (pintype "passive"))
    )
    (net (code "124") (name "unconnected-(S4-Pad3)") (class "Default")
      (node (ref "S4") (pin "3") (pinfunction "3_3") (pintype "passive"))
    )
    (net (code "125") (name "unconnected-(SD1-DAT1-Pad8)") (class "Default")
      (node (ref "SD1") (pin "8") (pinfunction "DAT1_8") (pintype "bidirectional"))
    )
    (net (code "126") (name "unconnected-(SD1-DAT2-Pad1)") (class "Default")
      (node (ref "SD1") (pin "1") (pinfunction "DAT2_1") (pintype "bidirectional"))
    )
    (net (code "127") (name "unconnected-(SD1-~{CARD}-Pad9)") (class "Default")
      (node (ref "SD1") (pin "9") (pinfunction "~{CARD}_9") (pintype "passive"))
    )
  )
)
